# tempmux.net
KiCad netlist of a schematic drawn in Altium Designer
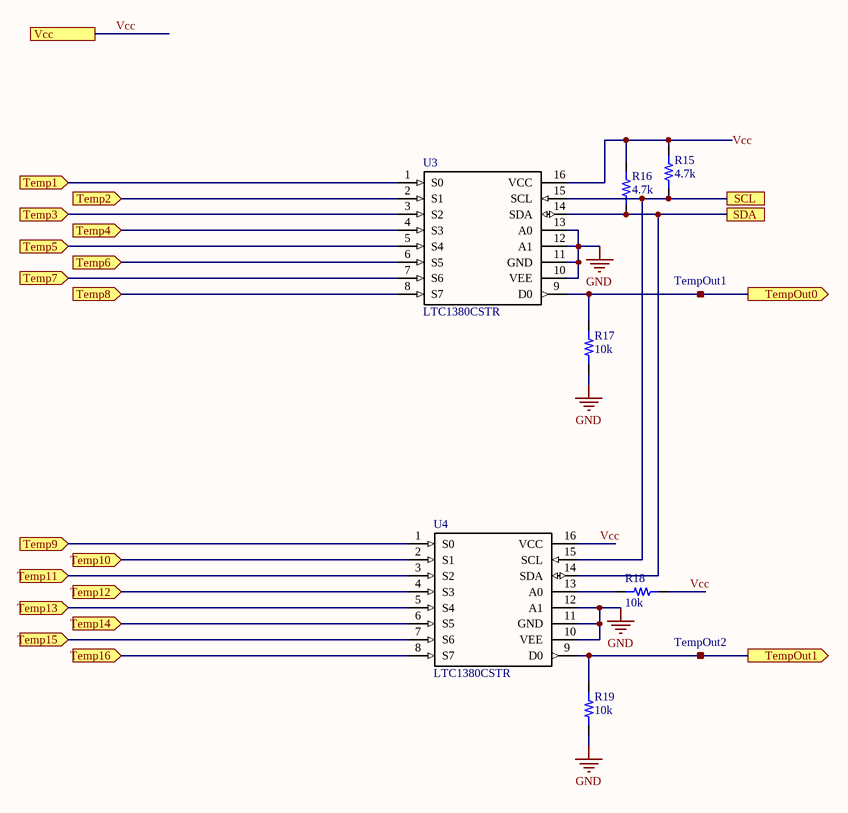
[diagram p0: tempmux.SchDoc]

(export (version "E")
  (design (tool "Eeschema 10.0.6"))
  (components
    (comp (ref "R15")
      (value "4.7k")
      (footprint "RES 0603/1608")
      (fields (field (name "RESISTANCE") "4.7k"))
      (libsource (lib "altlib") (part "Resistor"))
    )
    (comp (ref "R16")
      (value "4.7k")
      (footprint "RES 0603/1608")
      (fields (field (name "RESISTANCE") "4.7k"))
      (libsource (lib "altlib") (part "Resistor"))
    )
    (comp (ref "R17")
      (value "10k")
      (footprint "RES 0603/1608")
      (fields (field (name "RESISTANCE") "10k"))
      (libsource (lib "altlib") (part "Resistor"))
    )
    (comp (ref "R18")
      (value "10k")
      (footprint "RES 0603/1608")
      (fields (field (name "RESISTANCE") "10k"))
      (libsource (lib "altlib") (part "Resistor"))
    )
    (comp (ref "R19")
      (value "10k")
      (footprint "RES 0603/1608")
      (fields (field (name "RESISTANCE") "10k"))
      (libsource (lib "altlib") (part "Resistor"))
    )
    (comp (ref "TempOut1") (value "RCU-0C") (footprint "RCU-0C") (libsource (lib "altlib") (part "RCU-0C")))
    (comp (ref "TempOut2") (value "RCU-0C") (footprint "RCU-0C") (libsource (lib "altlib") (part "RCU-0C")))
    (comp (ref "U3")
      (value "LTC1380CSTR")
      (footprint "LTC1380CSTR")
      (description "8:1 analog multiplexer. I2C interface. 2 address pins.")
      (fields (field (name "CREATEDBY") "Haley Pierce") (field (name "UPDATEDBY") "0"))
      (libsource (lib "altlib") (part "LTC1380CSTR"))
    )
    (comp (ref "U4")
      (value "LTC1380CSTR")
      (footprint "LTC1380CSTR")
      (description "8:1 analog multiplexer. I2C interface. 2 address pins.")
      (fields (field (name "CREATEDBY") "Haley Pierce") (field (name "UPDATEDBY") "0"))
      (libsource (lib "altlib") (part "LTC1380CSTR"))
    )
  )
  (nets
    (net (code "1") (name "/SCL") (class "Default")
      (node (ref "R15") (pin "1") (pinfunction "1_1") (pintype "passive"))
      (node (ref "U3") (pin "15") (pinfunction "SCL_15") (pintype "input"))
      (node (ref "U4") (pin "15") (pinfunction "SCL_15") (pintype "input"))
    )
    (net (code "2") (name "/SDA") (class "Default")
      (node (ref "R16") (pin "1") (pinfunction "1_1") (pintype "passive"))
      (node (ref "U3") (pin "14") (pinfunction "SDA_14") (pintype "bidirectional"))
      (node (ref "U4") (pin "14") (pinfunction "SDA_14") (pintype "bidirectional"))
    )
    (net (code "3") (name "/Temp1") (class "Default")
      (node (ref "U3") (pin "1") (pinfunction "S0_1") (pintype "input"))
    )
    (net (code "4") (name "/Temp2") (class "Default")
      (node (ref "U3") (pin "2") (pinfunction "S1_2") (pintype "input"))
    )
    (net (code "5") (name "/Temp3") (class "Default")
      (node (ref "U3") (pin "3") (pinfunction "S2_3") (pintype "input"))
    )
    (net (code "6") (name "/Temp4") (class "Default")
      (node (ref "U3") (pin "4") (pinfunction "S3_4") (pintype "input"))
    )
    (net (code "7") (name "/Temp5") (class "Default")
      (node (ref "U3") (pin "5") (pinfunction "S4_5") (pintype "input"))
    )
    (net (code "8") (name "/Temp6") (class "Default")
      (node (ref "U3") (pin "6") (pinfunction "S5_6") (pintype "input"))
    )
    (net (code "9") (name "/Temp7") (class "Default")
      (node (ref "U3") (pin "7") (pinfunction "S6_7") (pintype "input"))
    )
    (net (code "10") (name "/Temp8") (class "Default")
      (node (ref "U3") (pin "8") (pinfunction "S7_8") (pintype "input"))
    )
    (net (code "11") (name "/Temp9") (class "Default")
      (node (ref "U4") (pin "1") (pinfunction "S0_1") (pintype "input"))
    )
    (net (code "12") (name "/Temp10") (class "Default")
      (node (ref "U4") (pin "2") (pinfunction "S1_2") (pintype "input"))
    )
    (net (code "13") (name "/Temp11") (class "Default")
      (node (ref "U4") (pin "3") (pinfunction "S2_3") (pintype "input"))
    )
    (net (code "14") (name "/Temp12") (class "Default")
      (node (ref "U4") (pin "4") (pinfunction "S3_4") (pintype "input"))
    )
    (net (code "15") (name "/Temp13") (class "Default")
      (node (ref "U4") (pin "5") (pinfunction "S4_5") (pintype "input"))
    )
    (net (code "16") (name "/Temp14") (class "Default")
      (node (ref "U4") (pin "6") (pinfunction "S5_6") (pintype "input"))
    )
    (net (code "17") (name "/Temp15") (class "Default")
      (node (ref "U4") (pin "7") (pinfunction "S6_7") (pintype "input"))
    )
    (net (code "18") (name "/Temp16") (class "Default")
      (node (ref "U4") (pin "8") (pinfunction "S7_8") (pintype "input"))
    )
    (net (code "19") (name "/TempOut0") (class "Default")
      (node (ref "R17") (pin "2") (pinfunction "2_2") (pintype "passive"))
      (node (ref "TempOut1") (pin "1") (pintype "passive"))
      (node (ref "U3") (pin "9") (pinfunction "D0_9") (pintype "output"))
    )
    (net (code "20") (name "/TempOut1") (class "Default")
      (node (ref "R19") (pin "2") (pinfunction "2_2") (pintype "passive"))
      (node (ref "TempOut2") (pin "1") (pintype "passive"))
      (node (ref "U4") (pin "9") (pinfunction "D0_9") (pintype "output"))
    )
    (net (code "21") (name "/Vcc") (class "Default")
      (node (ref "R15") (pin "2") (pinfunction "2_2") (pintype "passive"))
      (node (ref "R16") (pin "2") (pinfunction "2_2") (pintype "passive"))
      (node (ref "R18") (pin "2") (pinfunction "2_2") (pintype "passive"))
      (node (ref "U3") (pin "16") (pinfunction "VCC_16") (pintype "passive"))
      (node (ref "U4") (pin "16") (pinfunction "VCC_16") (pintype "passive"))
    )
    (net (code "22") (name "GND") (class "Default")
      (node (ref "R17") (pin "1") (pinfunction "1_1") (pintype "passive"))
      (node (ref "R19") (pin "1") (pinfunction "1_1") (pintype "passive"))
      (node (ref "U3") (pin "10") (pinfunction "VEE_10") (pintype "passive"))
      (node (ref "U3") (pin "11") (pinfunction "GND_11") (pintype "passive"))
      (node (ref "U3") (pin "12") (pinfunction "A1_12") (pintype "passive"))
      (node (ref "U3") (pin "13") (pinfunction "A0_13") (pintype "passive"))
      (node (ref "U4") (pin "10") (pinfunction "VEE_10") (pintype "passive"))
      (node (ref "U4") (pin "11") (pinfunction "GND_11") (pintype "passive"))
      (node (ref "U4") (pin "12") (pinfunction "A1_12") (pintype "passive"))
    )
    (net (code "23") (name "Net-(U4-A0)") (class "Default")
      (node (ref "R18") (pin "1") (pinfunction "1_1") (pintype "passive"))
      (node (ref "U4") (pin "13") (pinfunction "A0_13") (pintype "passive"))
    )
  )
)
